# OneRCSchematic_v1_8.net
KiCad netlist of a schematic drawn in EAGLE
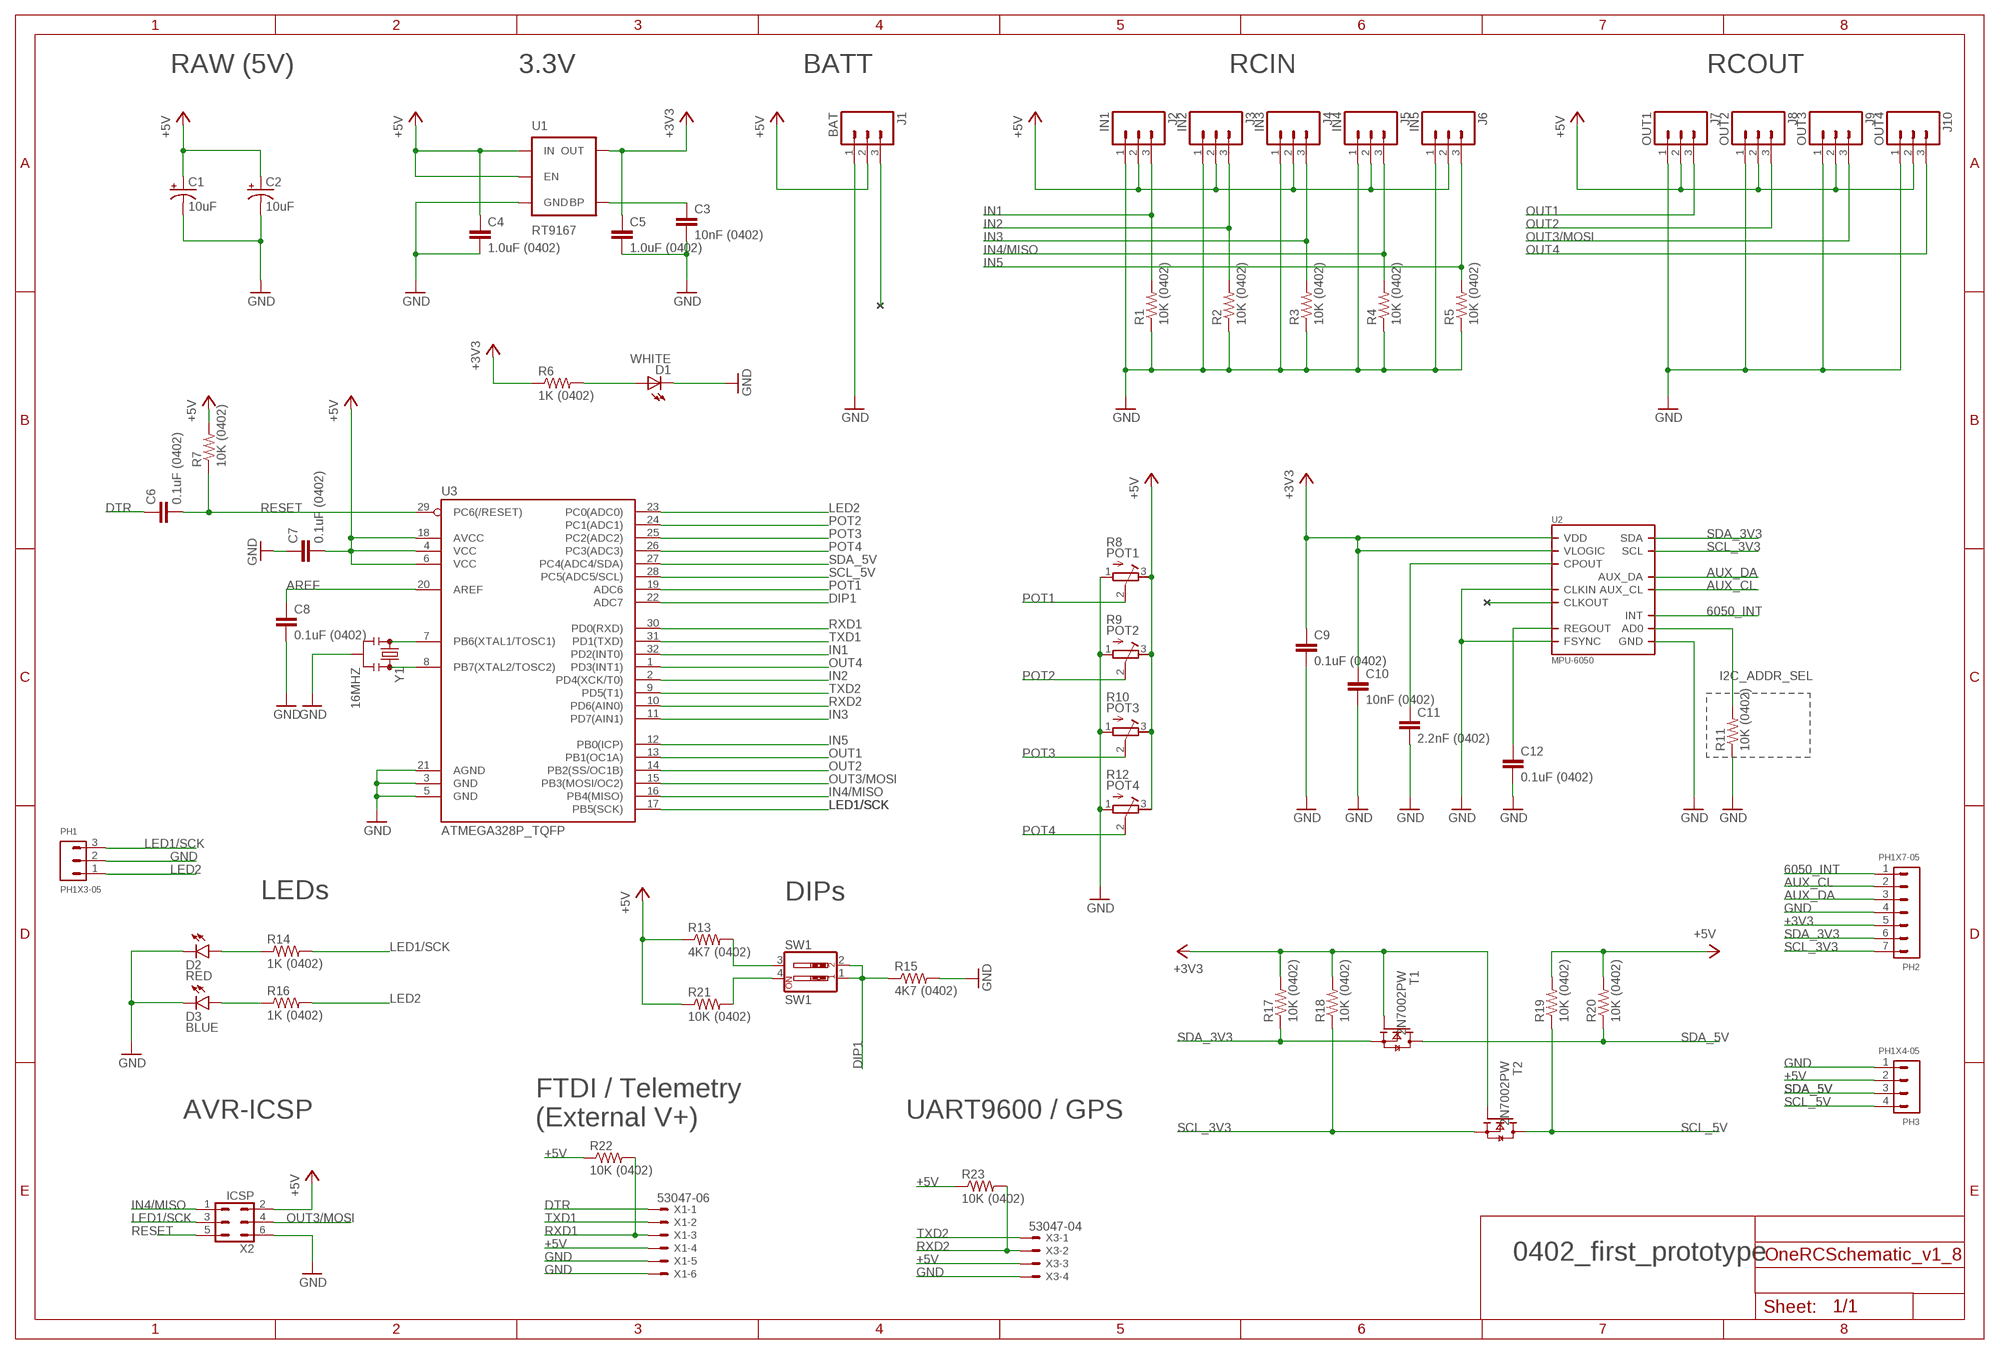
[diagram p0: schematic, sheet 1]

(export (version "E")
  (design (tool "Eeschema 10.0.6"))
  (components
    (comp (ref "C1")
      (value "10uF")
      (footprint "eagle-import:EIA3216")
      (libsource (lib "eagle-import") (part "10UF-16V-10%(TANT)"))
    )
    (comp (ref "C2")
      (value "10uF")
      (footprint "eagle-import:EIA3216")
      (libsource (lib "eagle-import") (part "10UF-16V-10%(TANT)"))
    )
    (comp (ref "C3")
      (value "10nF (0402)")
      (footprint "eagle-import:0402-CAP")
      (libsource (lib "eagle-import") (part "CAP0402-CAP"))
    )
    (comp (ref "C4")
      (value "1.0uF (0402)")
      (footprint "eagle-import:0402-CAP")
      (libsource (lib "eagle-import") (part "CAP0402-CAP"))
    )
    (comp (ref "C5")
      (value "1.0uF (0402)")
      (footprint "eagle-import:0402-CAP")
      (libsource (lib "eagle-import") (part "CAP0402-CAP"))
    )
    (comp (ref "C6")
      (value "0.1uF (0402)")
      (footprint "eagle-import:0402-CAP")
      (libsource (lib "eagle-import") (part "CAP0402-CAP"))
    )
    (comp (ref "C7")
      (value "0.1uF (0402)")
      (footprint "eagle-import:0402-CAP")
      (libsource (lib "eagle-import") (part "CAP0402-CAP"))
    )
    (comp (ref "C8")
      (value "0.1uF (0402)")
      (footprint "eagle-import:0402-CAP")
      (libsource (lib "eagle-import") (part "CAP0402-CAP"))
    )
    (comp (ref "C9")
      (value "0.1uF (0402)")
      (footprint "eagle-import:0402-CAP")
      (libsource (lib "eagle-import") (part "CAP0402-CAP"))
    )
    (comp (ref "C10")
      (value "10nF (0402)")
      (footprint "eagle-import:0402-CAP")
      (libsource (lib "eagle-import") (part "CAP0402-CAP"))
    )
    (comp (ref "C11")
      (value "2.2nF (0402)")
      (footprint "eagle-import:0402-CAP")
      (libsource (lib "eagle-import") (part "CAP0402-CAP"))
    )
    (comp (ref "C12")
      (value "0.1uF (0402)")
      (footprint "eagle-import:0402-CAP")
      (libsource (lib "eagle-import") (part "CAP0402-CAP"))
    )
    (comp (ref "D1")
      (value "WHITE")
      (footprint "eagle-import:0402-LED")
      (libsource (lib "eagle-import") (part "LED-0402"))
    )
    (comp (ref "D2")
      (value "RED")
      (footprint "eagle-import:LED-0603")
      (libsource (lib "eagle-import") (part "LED-RED0603"))
    )
    (comp (ref "D3")
      (value "BLUE")
      (footprint "eagle-import:LED-0603")
      (libsource (lib "eagle-import") (part "LED-BLUE0603"))
    )
    (comp (ref "J1")
      (value "BAT")
      (footprint "eagle-import:1X03")
      (libsource (lib "eagle-import") (part "M03PTH"))
    )
    (comp (ref "J2")
      (value "IN1")
      (footprint "eagle-import:1X03")
      (libsource (lib "eagle-import") (part "M03PTH"))
    )
    (comp (ref "J3")
      (value "IN2")
      (footprint "eagle-import:1X03")
      (libsource (lib "eagle-import") (part "M03PTH"))
    )
    (comp (ref "J4")
      (value "IN3")
      (footprint "eagle-import:1X03")
      (libsource (lib "eagle-import") (part "M03PTH"))
    )
    (comp (ref "J5")
      (value "IN4")
      (footprint "eagle-import:1X03")
      (libsource (lib "eagle-import") (part "M03PTH"))
    )
    (comp (ref "J6")
      (value "IN5")
      (footprint "eagle-import:1X03")
      (libsource (lib "eagle-import") (part "M03PTH"))
    )
    (comp (ref "J7")
      (value "OUT1")
      (footprint "eagle-import:1X03")
      (libsource (lib "eagle-import") (part "M03PTH"))
    )
    (comp (ref "J8")
      (value "OUT2")
      (footprint "eagle-import:1X03")
      (libsource (lib "eagle-import") (part "M03PTH"))
    )
    (comp (ref "J9")
      (value "OUT3")
      (footprint "eagle-import:1X03")
      (libsource (lib "eagle-import") (part "M03PTH"))
    )
    (comp (ref "J10")
      (value "OUT4")
      (footprint "eagle-import:1X03")
      (libsource (lib "eagle-import") (part "M03PTH"))
    )
    (comp (ref "PH1")
      (value "PH1X3-05")
      (footprint "eagle-import:PH005-1-3")
      (libsource (lib "eagle-import") (part "PH1X3-05"))
    )
    (comp (ref "PH2")
      (value "PH1X7-05")
      (footprint "eagle-import:PH005-1-7")
      (libsource (lib "eagle-import") (part "PH1X7-05"))
    )
    (comp (ref "PH3")
      (value "PH1X4-05")
      (footprint "eagle-import:PH005-1-4")
      (libsource (lib "eagle-import") (part "PH1X4-05"))
    )
    (comp (ref "R1")
      (value "10K (0402)")
      (footprint "eagle-import:0402-RES")
      (libsource (lib "eagle-import") (part "RESISTOR0402"))
    )
    (comp (ref "R2")
      (value "10K (0402)")
      (footprint "eagle-import:0402-RES")
      (libsource (lib "eagle-import") (part "RESISTOR0402"))
    )
    (comp (ref "R3")
      (value "10K (0402)")
      (footprint "eagle-import:0402-RES")
      (libsource (lib "eagle-import") (part "RESISTOR0402"))
    )
    (comp (ref "R4")
      (value "10K (0402)")
      (footprint "eagle-import:0402-RES")
      (libsource (lib "eagle-import") (part "RESISTOR0402"))
    )
    (comp (ref "R5")
      (value "10K (0402)")
      (footprint "eagle-import:0402-RES")
      (libsource (lib "eagle-import") (part "RESISTOR0402"))
    )
    (comp (ref "R6")
      (value "1K (0402)")
      (footprint "eagle-import:0402-RES")
      (libsource (lib "eagle-import") (part "RESISTOR0402"))
    )
    (comp (ref "R7")
      (value "10K (0402)")
      (footprint "eagle-import:0402-RES")
      (libsource (lib "eagle-import") (part "RESISTOR0402"))
    )
    (comp (ref "R8")
      (value "POT1")
      (footprint "eagle-import:RTRIM3202")
      (libsource (lib "eagle-import") (part "R-TRIMM3202"))
    )
    (comp (ref "R9")
      (value "POT2")
      (footprint "eagle-import:RTRIM3202")
      (libsource (lib "eagle-import") (part "R-TRIMM3202"))
    )
    (comp (ref "R10")
      (value "POT3")
      (footprint "eagle-import:RTRIM3202")
      (libsource (lib "eagle-import") (part "R-TRIMM3202"))
    )
    (comp (ref "R11")
      (value "10K (0402)")
      (footprint "eagle-import:0402-RES")
      (libsource (lib "eagle-import") (part "RESISTOR0402"))
    )
    (comp (ref "R12")
      (value "POT4")
      (footprint "eagle-import:RTRIM3202")
      (libsource (lib "eagle-import") (part "R-TRIMM3202"))
    )
    (comp (ref "R13")
      (value "4K7 (0402)")
      (footprint "eagle-import:0402-RES")
      (libsource (lib "eagle-import") (part "RESISTOR0402"))
    )
    (comp (ref "R14")
      (value "1K (0402)")
      (footprint "eagle-import:0402-RES")
      (libsource (lib "eagle-import") (part "RESISTOR0402"))
    )
    (comp (ref "R15")
      (value "4K7 (0402)")
      (footprint "eagle-import:0402-RES")
      (libsource (lib "eagle-import") (part "RESISTOR0402"))
    )
    (comp (ref "R16")
      (value "1K (0402)")
      (footprint "eagle-import:0402-RES")
      (libsource (lib "eagle-import") (part "RESISTOR0402"))
    )
    (comp (ref "R17")
      (value "10K (0402)")
      (footprint "eagle-import:0402-RES")
      (libsource (lib "eagle-import") (part "RESISTOR0402"))
    )
    (comp (ref "R18")
      (value "10K (0402)")
      (footprint "eagle-import:0402-RES")
      (libsource (lib "eagle-import") (part "RESISTOR0402"))
    )
    (comp (ref "R19")
      (value "10K (0402)")
      (footprint "eagle-import:0402-RES")
      (libsource (lib "eagle-import") (part "RESISTOR0402"))
    )
    (comp (ref "R20")
      (value "10K (0402)")
      (footprint "eagle-import:0402-RES")
      (libsource (lib "eagle-import") (part "RESISTOR0402"))
    )
    (comp (ref "R21")
      (value "10K (0402)")
      (footprint "eagle-import:0402-RES")
      (libsource (lib "eagle-import") (part "RESISTOR0402"))
    )
    (comp (ref "R22")
      (value "10K (0402)")
      (footprint "eagle-import:0402-RES")
      (libsource (lib "eagle-import") (part "RESISTOR0402"))
    )
    (comp (ref "R23")
      (value "10K (0402)")
      (footprint "eagle-import:0402-RES")
      (libsource (lib "eagle-import") (part "RESISTOR0402"))
    )
    (comp (ref "SW1")
      (value "SW1")
      (footprint "eagle-import:DIPSWITCH-02-50MIL")
      (libsource (lib "eagle-import") (part "SW_DIP-2-SMT-HALFSIZE"))
    )
    (comp (ref "T1")
      (value "2N7002PW")
      (footprint "eagle-import:SOT323")
      (libsource (lib "eagle-import") (part "2N7002PW"))
    )
    (comp (ref "T2")
      (value "2N7002PW")
      (footprint "eagle-import:SOT323")
      (libsource (lib "eagle-import") (part "2N7002PW"))
    )
    (comp (ref "U1")
      (value "RT9167")
      (footprint "eagle-import:SOT23-5")
      (libsource (lib "eagle-import") (part "MIC52053.3V"))
    )
    (comp (ref "U2")
      (value "MPU-6050")
      (footprint "eagle-import:QFN.24.4X4")
      (libsource (lib "eagle-import") (part "MPU-6050"))
    )
    (comp (ref "U3")
      (value "ATMEGA328P_TQFP")
      (footprint "eagle-import:TQFP32-08")
      (libsource (lib "eagle-import") (part "ATMEGA328P_TQFP"))
    )
    (comp (ref "X1")
      (value "53047-06")
      (footprint "eagle-import:53047-06")
      (fields (field (name "MPN") "53047-0610-C"))
      (libsource (lib "eagle-import") (part "53?-06047"))
    )
    (comp (ref "X2")
      (value "ICSP")
      (footprint "eagle-import:PHB_1MM27_2X03_SNT")
      (libsource (lib "eagle-import") (part "PHB_1MM27_2X03_SNT"))
    )
    (comp (ref "X3")
      (value "53047-04")
      (footprint "eagle-import:53047-04")
      (fields (field (name "MF") "WALDOM/MOLEX") (field (name "MPN") "53047-0410"))
      (libsource (lib "eagle-import") (part "53?-04047"))
    )
    (comp (ref "Y1")
      (value "16MHZ")
      (footprint "eagle-import:RESONATOR-SMD")
      (libsource (lib "eagle-import") (part "RESONATOR16MHZ"))
    )
  )
  (nets
    (net (code "1") (name "+3V3") (class "Default")
      (node (ref "C10") (pin "1") (pinfunction "1_1") (pintype "passive"))
      (node (ref "C5") (pin "1") (pinfunction "1_1") (pintype "passive"))
      (node (ref "C9") (pin "1") (pinfunction "1_1") (pintype "passive"))
      (node (ref "PH2") (pin "5") (pinfunction "5_5") (pintype "bidirectional"))
      (node (ref "R17") (pin "2") (pinfunction "2_2") (pintype "passive"))
      (node (ref "R18") (pin "2") (pinfunction "2_2") (pintype "passive"))
      (node (ref "R6") (pin "1") (pinfunction "1_1") (pintype "passive"))
      (node (ref "T1") (pin "1") (pinfunction "G_1") (pintype "passive"))
      (node (ref "T2") (pin "1") (pinfunction "G_1") (pintype "passive"))
      (node (ref "U1") (pin "5") (pinfunction "OUT_5") (pintype "passive"))
      (node (ref "U2") (pin "13") (pinfunction "VDD_13") (pintype "bidirectional"))
      (node (ref "U2") (pin "8") (pinfunction "VLOGIC_8") (pintype "bidirectional"))
    )
    (net (code "2") (name "+5V") (class "Default")
      (node (ref "C1") (pin "A") (pinfunction "+_A") (pintype "passive"))
      (node (ref "C2") (pin "A") (pinfunction "+_A") (pintype "passive"))
      (node (ref "C4") (pin "1") (pinfunction "1_1") (pintype "passive"))
      (node (ref "C7") (pin "2") (pinfunction "2_2") (pintype "passive"))
      (node (ref "J1") (pin "2") (pinfunction "2_2") (pintype "passive"))
      (node (ref "J10") (pin "2") (pinfunction "2_2") (pintype "passive"))
      (node (ref "J2") (pin "2") (pinfunction "2_2") (pintype "passive"))
      (node (ref "J3") (pin "2") (pinfunction "2_2") (pintype "passive"))
      (node (ref "J4") (pin "2") (pinfunction "2_2") (pintype "passive"))
      (node (ref "J5") (pin "2") (pinfunction "2_2") (pintype "passive"))
      (node (ref "J6") (pin "2") (pinfunction "2_2") (pintype "passive"))
      (node (ref "J7") (pin "2") (pinfunction "2_2") (pintype "passive"))
      (node (ref "J8") (pin "2") (pinfunction "2_2") (pintype "passive"))
      (node (ref "J9") (pin "2") (pinfunction "2_2") (pintype "passive"))
      (node (ref "PH3") (pin "2") (pinfunction "2_2") (pintype "bidirectional"))
      (node (ref "R10") (pin "3") (pinfunction "E_3") (pintype "passive"))
      (node (ref "R12") (pin "3") (pinfunction "E_3") (pintype "passive"))
      (node (ref "R13") (pin "1") (pinfunction "1_1") (pintype "passive"))
      (node (ref "R19") (pin "2") (pinfunction "2_2") (pintype "passive"))
      (node (ref "R20") (pin "2") (pinfunction "2_2") (pintype "passive"))
      (node (ref "R21") (pin "1") (pinfunction "1_1") (pintype "passive"))
      (node (ref "R22") (pin "1") (pinfunction "1_1") (pintype "passive"))
      (node (ref "R23") (pin "1") (pinfunction "1_1") (pintype "passive"))
      (node (ref "R7") (pin "2") (pinfunction "2_2") (pintype "passive"))
      (node (ref "R8") (pin "3") (pinfunction "E_3") (pintype "passive"))
      (node (ref "R9") (pin "3") (pinfunction "E_3") (pintype "passive"))
      (node (ref "U1") (pin "1") (pinfunction "IN_1") (pintype "input"))
      (node (ref "U1") (pin "3") (pinfunction "EN_3") (pintype "input"))
      (node (ref "U3") (pin "18") (pinfunction "AVCC_18") (pintype "bidirectional"))
      (node (ref "U3") (pin "4") (pinfunction "VCC_4") (pintype "bidirectional"))
      (node (ref "U3") (pin "6") (pinfunction "VCC_6") (pintype "bidirectional"))
      (node (ref "X1") (pin "4") (pinfunction "S_4") (pintype "passive"))
      (node (ref "X2") (pin "2") (pinfunction "2_2") (pintype "passive"))
      (node (ref "X3") (pin "3") (pinfunction "S_3") (pintype "passive"))
    )
    (net (code "3") (name "/6050_INT") (class "Default")
      (node (ref "PH2") (pin "1") (pinfunction "1_1") (pintype "bidirectional"))
      (node (ref "U2") (pin "12") (pinfunction "INT_12") (pintype "bidirectional"))
    )
    (net (code "4") (name "/AREF") (class "Default")
      (node (ref "C8") (pin "1") (pinfunction "1_1") (pintype "passive"))
      (node (ref "U3") (pin "20") (pinfunction "AREF_20") (pintype "bidirectional"))
    )
    (net (code "5") (name "/AUX_CL") (class "Default")
      (node (ref "PH2") (pin "2") (pinfunction "2_2") (pintype "bidirectional"))
      (node (ref "U2") (pin "7") (pinfunction "AUX_CL_7") (pintype "bidirectional"))
    )
    (net (code "6") (name "/AUX_DA") (class "Default")
      (node (ref "PH2") (pin "3") (pinfunction "3_3") (pintype "bidirectional"))
      (node (ref "U2") (pin "6") (pinfunction "AUX_DA_6") (pintype "bidirectional"))
    )
    (net (code "7") (name "/DIP1") (class "Default")
      (node (ref "R15") (pin "1") (pinfunction "1_1") (pintype "passive"))
      (node (ref "SW1") (pin "1") (pinfunction "1_1") (pintype "passive"))
      (node (ref "SW1") (pin "2") (pinfunction "2_2") (pintype "passive"))
      (node (ref "U3") (pin "22") (pinfunction "ADC7_22") (pintype "bidirectional"))
    )
    (net (code "8") (name "/DTR") (class "Default")
      (node (ref "C6") (pin "1") (pinfunction "1_1") (pintype "passive"))
      (node (ref "X1") (pin "1") (pinfunction "S_1") (pintype "passive"))
    )
    (net (code "9") (name "/IN1") (class "Default")
      (node (ref "J2") (pin "3") (pinfunction "3_3") (pintype "passive"))
      (node (ref "R1") (pin "2") (pinfunction "2_2") (pintype "passive"))
      (node (ref "U3") (pin "32") (pinfunction "PD2(INT0)_32") (pintype "bidirectional"))
    )
    (net (code "10") (name "/IN2") (class "Default")
      (node (ref "J3") (pin "3") (pinfunction "3_3") (pintype "passive"))
      (node (ref "R2") (pin "2") (pinfunction "2_2") (pintype "passive"))
      (node (ref "U3") (pin "2") (pinfunction "PD4(XCK/T0)_2") (pintype "bidirectional"))
    )
    (net (code "11") (name "/IN3") (class "Default")
      (node (ref "J4") (pin "3") (pinfunction "3_3") (pintype "passive"))
      (node (ref "R3") (pin "2") (pinfunction "2_2") (pintype "passive"))
      (node (ref "U3") (pin "11") (pinfunction "PD7(AIN1)_11") (pintype "bidirectional"))
    )
    (net (code "12") (name "/IN4{slash}MISO") (class "Default")
      (node (ref "J5") (pin "3") (pinfunction "3_3") (pintype "passive"))
      (node (ref "R4") (pin "2") (pinfunction "2_2") (pintype "passive"))
      (node (ref "U3") (pin "16") (pinfunction "PB4(MISO)_16") (pintype "bidirectional"))
      (node (ref "X2") (pin "1") (pinfunction "1_1") (pintype "passive"))
    )
    (net (code "13") (name "/IN5") (class "Default")
      (node (ref "J6") (pin "3") (pinfunction "3_3") (pintype "passive"))
      (node (ref "R5") (pin "2") (pinfunction "2_2") (pintype "passive"))
      (node (ref "U3") (pin "12") (pinfunction "PB0(ICP)_12") (pintype "bidirectional"))
    )
    (net (code "14") (name "/LED1{slash}SCK") (class "Default")
      (node (ref "PH1") (pin "3") (pinfunction "3_3") (pintype "bidirectional"))
      (node (ref "R14") (pin "2") (pinfunction "2_2") (pintype "passive"))
      (node (ref "U3") (pin "17") (pinfunction "PB5(SCK)_17") (pintype "bidirectional"))
      (node (ref "X2") (pin "3") (pinfunction "3_3") (pintype "passive"))
    )
    (net (code "15") (name "/LED2") (class "Default")
      (node (ref "PH1") (pin "1") (pinfunction "1_1") (pintype "bidirectional"))
      (node (ref "R16") (pin "2") (pinfunction "2_2") (pintype "passive"))
      (node (ref "U3") (pin "23") (pinfunction "PC0(ADC0)_23") (pintype "bidirectional"))
    )
    (net (code "16") (name "/OUT1") (class "Default")
      (node (ref "J7") (pin "3") (pinfunction "3_3") (pintype "passive"))
      (node (ref "U3") (pin "13") (pinfunction "PB1(OC1A)_13") (pintype "bidirectional"))
    )
    (net (code "17") (name "/OUT2") (class "Default")
      (node (ref "J8") (pin "3") (pinfunction "3_3") (pintype "passive"))
      (node (ref "U3") (pin "14") (pinfunction "PB2(SS/OC1B)_14") (pintype "bidirectional"))
    )
    (net (code "18") (name "/OUT3{slash}MOSI") (class "Default")
      (node (ref "J9") (pin "3") (pinfunction "3_3") (pintype "passive"))
      (node (ref "U3") (pin "15") (pinfunction "PB3(MOSI/OC2)_15") (pintype "bidirectional"))
      (node (ref "X2") (pin "4") (pinfunction "4_4") (pintype "passive"))
    )
    (net (code "19") (name "/OUT4") (class "Default")
      (node (ref "J10") (pin "3") (pinfunction "3_3") (pintype "passive"))
      (node (ref "U3") (pin "1") (pinfunction "PD3(INT1)_1") (pintype "bidirectional"))
    )
    (net (code "20") (name "/POT1") (class "Default")
      (node (ref "R8") (pin "2") (pinfunction "S_2") (pintype "passive"))
      (node (ref "U3") (pin "19") (pinfunction "ADC6_19") (pintype "bidirectional"))
    )
    (net (code "21") (name "/POT2") (class "Default")
      (node (ref "R9") (pin "2") (pinfunction "S_2") (pintype "passive"))
      (node (ref "U3") (pin "24") (pinfunction "PC1(ADC1)_24") (pintype "bidirectional"))
    )
    (net (code "22") (name "/POT3") (class "Default")
      (node (ref "R10") (pin "2") (pinfunction "S_2") (pintype "passive"))
      (node (ref "U3") (pin "25") (pinfunction "PC2(ADC2)_25") (pintype "bidirectional"))
    )
    (net (code "23") (name "/POT4") (class "Default")
      (node (ref "R12") (pin "2") (pinfunction "S_2") (pintype "passive"))
      (node (ref "U3") (pin "26") (pinfunction "PC3(ADC3)_26") (pintype "bidirectional"))
    )
    (net (code "24") (name "/RESET") (class "Default")
      (node (ref "C6") (pin "2") (pinfunction "2_2") (pintype "passive"))
      (node (ref "R7") (pin "1") (pinfunction "1_1") (pintype "passive"))
      (node (ref "U3") (pin "29") (pinfunction "PC6(/RESET)_29") (pintype "bidirectional"))
      (node (ref "X2") (pin "5") (pinfunction "5_5") (pintype "passive"))
    )
    (net (code "25") (name "/RXD1") (class "Default")
      (node (ref "R22") (pin "2") (pinfunction "2_2") (pintype "passive"))
      (node (ref "U3") (pin "30") (pinfunction "PD0(RXD)_30") (pintype "bidirectional"))
      (node (ref "X1") (pin "3") (pinfunction "S_3") (pintype "passive"))
    )
    (net (code "26") (name "/RXD2") (class "Default")
      (node (ref "R23") (pin "2") (pinfunction "2_2") (pintype "passive"))
      (node (ref "U3") (pin "10") (pinfunction "PD6(AIN0)_10") (pintype "bidirectional"))
      (node (ref "X3") (pin "2") (pinfunction "S_2") (pintype "passive"))
    )
    (net (code "27") (name "/SCL_3V3") (class "Default")
      (node (ref "PH2") (pin "7") (pinfunction "7_7") (pintype "bidirectional"))
      (node (ref "R18") (pin "1") (pinfunction "1_1") (pintype "passive"))
      (node (ref "T2") (pin "2") (pinfunction "S_2") (pintype "passive"))
      (node (ref "U2") (pin "23") (pinfunction "SCL_23") (pintype "bidirectional"))
    )
    (net (code "28") (name "/SCL_5V") (class "Default")
      (node (ref "PH3") (pin "4") (pinfunction "4_4") (pintype "bidirectional"))
      (node (ref "R19") (pin "1") (pinfunction "1_1") (pintype "passive"))
      (node (ref "T2") (pin "3") (pinfunction "D_3") (pintype "passive"))
      (node (ref "U3") (pin "28") (pinfunction "PC5(ADC5/SCL)_28") (pintype "bidirectional"))
    )
    (net (code "29") (name "/SDA_3V3") (class "Default")
      (node (ref "PH2") (pin "6") (pinfunction "6_6") (pintype "bidirectional"))
      (node (ref "R17") (pin "1") (pinfunction "1_1") (pintype "passive"))
      (node (ref "T1") (pin "2") (pinfunction "S_2") (pintype "passive"))
      (node (ref "U2") (pin "24") (pinfunction "SDA_24") (pintype "bidirectional"))
    )
    (net (code "30") (name "/SDA_5V") (class "Default")
      (node (ref "PH3") (pin "3") (pinfunction "3_3") (pintype "bidirectional"))
      (node (ref "R20") (pin "1") (pinfunction "1_1") (pintype "passive"))
      (node (ref "T1") (pin "3") (pinfunction "D_3") (pintype "passive"))
      (node (ref "U3") (pin "27") (pinfunction "PC4(ADC4/SDA)_27") (pintype "bidirectional"))
    )
    (net (code "31") (name "/TXD1") (class "Default")
      (node (ref "U3") (pin "31") (pinfunction "PD1(TXD)_31") (pintype "bidirectional"))
      (node (ref "X1") (pin "2") (pinfunction "S_2") (pintype "passive"))
    )
    (net (code "32") (name "/TXD2") (class "Default")
      (node (ref "U3") (pin "9") (pinfunction "PD5(T1)_9") (pintype "bidirectional"))
      (node (ref "X3") (pin "1") (pinfunction "S_1") (pintype "passive"))
    )
    (net (code "33") (name "GND") (class "Default")
      (node (ref "C1") (pin "C") (pinfunction "-_C") (pintype "passive"))
      (node (ref "C10") (pin "2") (pinfunction "2_2") (pintype "passive"))
      (node (ref "C11") (pin "2") (pinfunction "2_2") (pintype "passive"))
      (node (ref "C12") (pin "2") (pinfunction "2_2") (pintype "passive"))
      (node (ref "C2") (pin "C") (pinfunction "-_C") (pintype "passive"))
      (node (ref "C3") (pin "2") (pinfunction "2_2") (pintype "passive"))
      (node (ref "C4") (pin "2") (pinfunction "2_2") (pintype "passive"))
      (node (ref "C5") (pin "2") (pinfunction "2_2") (pintype "passive"))
      (node (ref "C7") (pin "1") (pinfunction "1_1") (pintype "passive"))
      (node (ref "C8") (pin "2") (pinfunction "2_2") (pintype "passive"))
      (node (ref "C9") (pin "2") (pinfunction "2_2") (pintype "passive"))
      (node (ref "D1") (pin "C") (pinfunction "C_C") (pintype "passive"))
      (node (ref "D2") (pin "C") (pinfunction "C_C") (pintype "passive"))
      (node (ref "D3") (pin "C") (pinfunction "C_C") (pintype "passive"))
      (node (ref "J1") (pin "1") (pinfunction "1_1") (pintype "passive"))
      (node (ref "J10") (pin "1") (pinfunction "1_1") (pintype "passive"))
      (node (ref "J2") (pin "1") (pinfunction "1_1") (pintype "passive"))
      (node (ref "J3") (pin "1") (pinfunction "1_1") (pintype "passive"))
      (node (ref "J4") (pin "1") (pinfunction "1_1") (pintype "passive"))
      (node (ref "J5") (pin "1") (pinfunction "1_1") (pintype "passive"))
      (node (ref "J6") (pin "1") (pinfunction "1_1") (pintype "passive"))
      (node (ref "J7") (pin "1") (pinfunction "1_1") (pintype "passive"))
      (node (ref "J8") (pin "1") (pinfunction "1_1") (pintype "passive"))
      (node (ref "J9") (pin "1") (pinfunction "1_1") (pintype "passive"))
      (node (ref "PH1") (pin "2") (pinfunction "2_2") (pintype "bidirectional"))
      (node (ref "PH2") (pin "4") (pinfunction "4_4") (pintype "bidirectional"))
      (node (ref "PH3") (pin "1") (pinfunction "1_1") (pintype "bidirectional"))
      (node (ref "R1") (pin "1") (pinfunction "1_1") (pintype "passive"))
      (node (ref "R10") (pin "1") (pinfunction "A_1") (pintype "passive"))
      (node (ref "R11") (pin "1") (pinfunction "1_1") (pintype "passive"))
      (node (ref "R12") (pin "1") (pinfunction "A_1") (pintype "passive"))
      (node (ref "R15") (pin "2") (pinfunction "2_2") (pintype "passive"))
      (node (ref "R2") (pin "1") (pinfunction "1_1") (pintype "passive"))
      (node (ref "R3") (pin "1") (pinfunction "1_1") (pintype "passive"))
      (node (ref "R4") (pin "1") (pinfunction "1_1") (pintype "passive"))
      (node (ref "R5") (pin "1") (pinfunction "1_1") (pintype "passive"))
      (node (ref "R8") (pin "1") (pinfunction "A_1") (pintype "passive"))
      (node (ref "R9") (pin "1") (pinfunction "A_1") (pintype "passive"))
      (node (ref "U1") (pin "2") (pinfunction "GND_2") (pintype "input"))
      (node (ref "U2") (pin "1") (pinfunction "CLKIN_1") (pintype "bidirectional"))
      (node (ref "U2") (pin "11") (pinfunction "FSYNC_11") (pintype "bidirectional"))
      (node (ref "U2") (pin "18") (pinfunction "GND_18") (pintype "bidirectional"))
      (node (ref "U3") (pin "21") (pinfunction "AGND_21") (pintype "bidirectional"))
      (node (ref "U3") (pin "3") (pinfunction "GND_3") (pintype "bidirectional"))
      (node (ref "U3") (pin "5") (pinfunction "GND_5") (pintype "bidirectional"))
      (node (ref "X1") (pin "5") (pinfunction "S_5") (pintype "passive"))
      (node (ref "X1") (pin "6") (pinfunction "S_6") (pintype "passive"))
      (node (ref "X2") (pin "6") (pinfunction "6_6") (pintype "passive"))
      (node (ref "X3") (pin "4") (pinfunction "S_4") (pintype "passive"))
      (node (ref "Y1") (pin "2") (pinfunction "2_2") (pintype "passive"))
    )
    (net (code "34") (name "Net-(D1-PadA)") (class "Default")
      (node (ref "D1") (pin "A") (pinfunction "A_A") (pintype "passive"))
      (node (ref "R6") (pin "2") (pinfunction "2_2") (pintype "passive"))
    )
    (net (code "35") (name "Net-(D2-PadA)") (class "Default")
      (node (ref "D2") (pin "A") (pinfunction "A_A") (pintype "passive"))
      (node (ref "R14") (pin "1") (pinfunction "1_1") (pintype "passive"))
    )
    (net (code "36") (name "Net-(D3-PadA)") (class "Default")
      (node (ref "D3") (pin "A") (pinfunction "A_A") (pintype "passive"))
      (node (ref "R16") (pin "1") (pinfunction "1_1") (pintype "passive"))
    )
    (net (code "37") (name "Net-(R13-Pad2)") (class "Default")
      (node (ref "R13") (pin "2") (pinfunction "2_2") (pintype "passive"))
      (node (ref "SW1") (pin "3") (pinfunction "3_3") (pintype "passive"))
    )
    (net (code "38") (name "Net-(R21-Pad2)") (class "Default")
      (node (ref "R21") (pin "2") (pinfunction "2_2") (pintype "passive"))
      (node (ref "SW1") (pin "4") (pinfunction "4_4") (pintype "passive"))
    )
    (net (code "39") (name "Net-(U1-BP)") (class "Default")
      (node (ref "C3") (pin "1") (pinfunction "1_1") (pintype "passive"))
      (node (ref "U1") (pin "4") (pinfunction "BP_4") (pintype "input"))
    )
    (net (code "40") (name "Net-(U2-AD0)") (class "Default")
      (node (ref "R11") (pin "2") (pinfunction "2_2") (pintype "passive"))
      (node (ref "U2") (pin "9") (pinfunction "AD0_9") (pintype "bidirectional"))
    )
    (net (code "41") (name "Net-(U2-CPOUT)") (class "Default")
      (node (ref "C11") (pin "1") (pinfunction "1_1") (pintype "passive"))
      (node (ref "U2") (pin "20") (pinfunction "CPOUT_20") (pintype "bidirectional"))
    )
    (net (code "42") (name "Net-(U2-REGOUT)") (class "Default")
      (node (ref "C12") (pin "1") (pinfunction "1_1") (pintype "passive"))
      (node (ref "U2") (pin "10") (pinfunction "REGOUT_10") (pintype "bidirectional"))
    )
    (net (code "43") (name "Net-(U3-PB6(XTAL1{slash}TOSC1))") (class "Default")
      (node (ref "U3") (pin "7") (pinfunction "PB6(XTAL1/TOSC1)_7") (pintype "bidirectional"))
      (node (ref "Y1") (pin "1") (pinfunction "1_1") (pintype "passive"))
    )
    (net (code "44") (name "Net-(U3-PB7(XTAL2{slash}TOSC2))") (class "Default")
      (node (ref "U3") (pin "8") (pinfunction "PB7(XTAL2/TOSC2)_8") (pintype "bidirectional"))
      (node (ref "Y1") (pin "3") (pinfunction "3_3") (pintype "passive"))
    )
    (net (code "45") (name "unconnected-(J1-Pad3)") (class "Default")
      (node (ref "J1") (pin "3") (pinfunction "3_3") (pintype "passive"))
    )
    (net (code "46") (name "unconnected-(U2-CLKOUT-Pad22)") (class "Default")
      (node (ref "U2") (pin "22") (pinfunction "CLKOUT_22") (pintype "bidirectional"))
    )
  )
)
